# k1fm-pico-balloon-v1_2.net
KiCad netlist of a schematic drawn in EAGLE
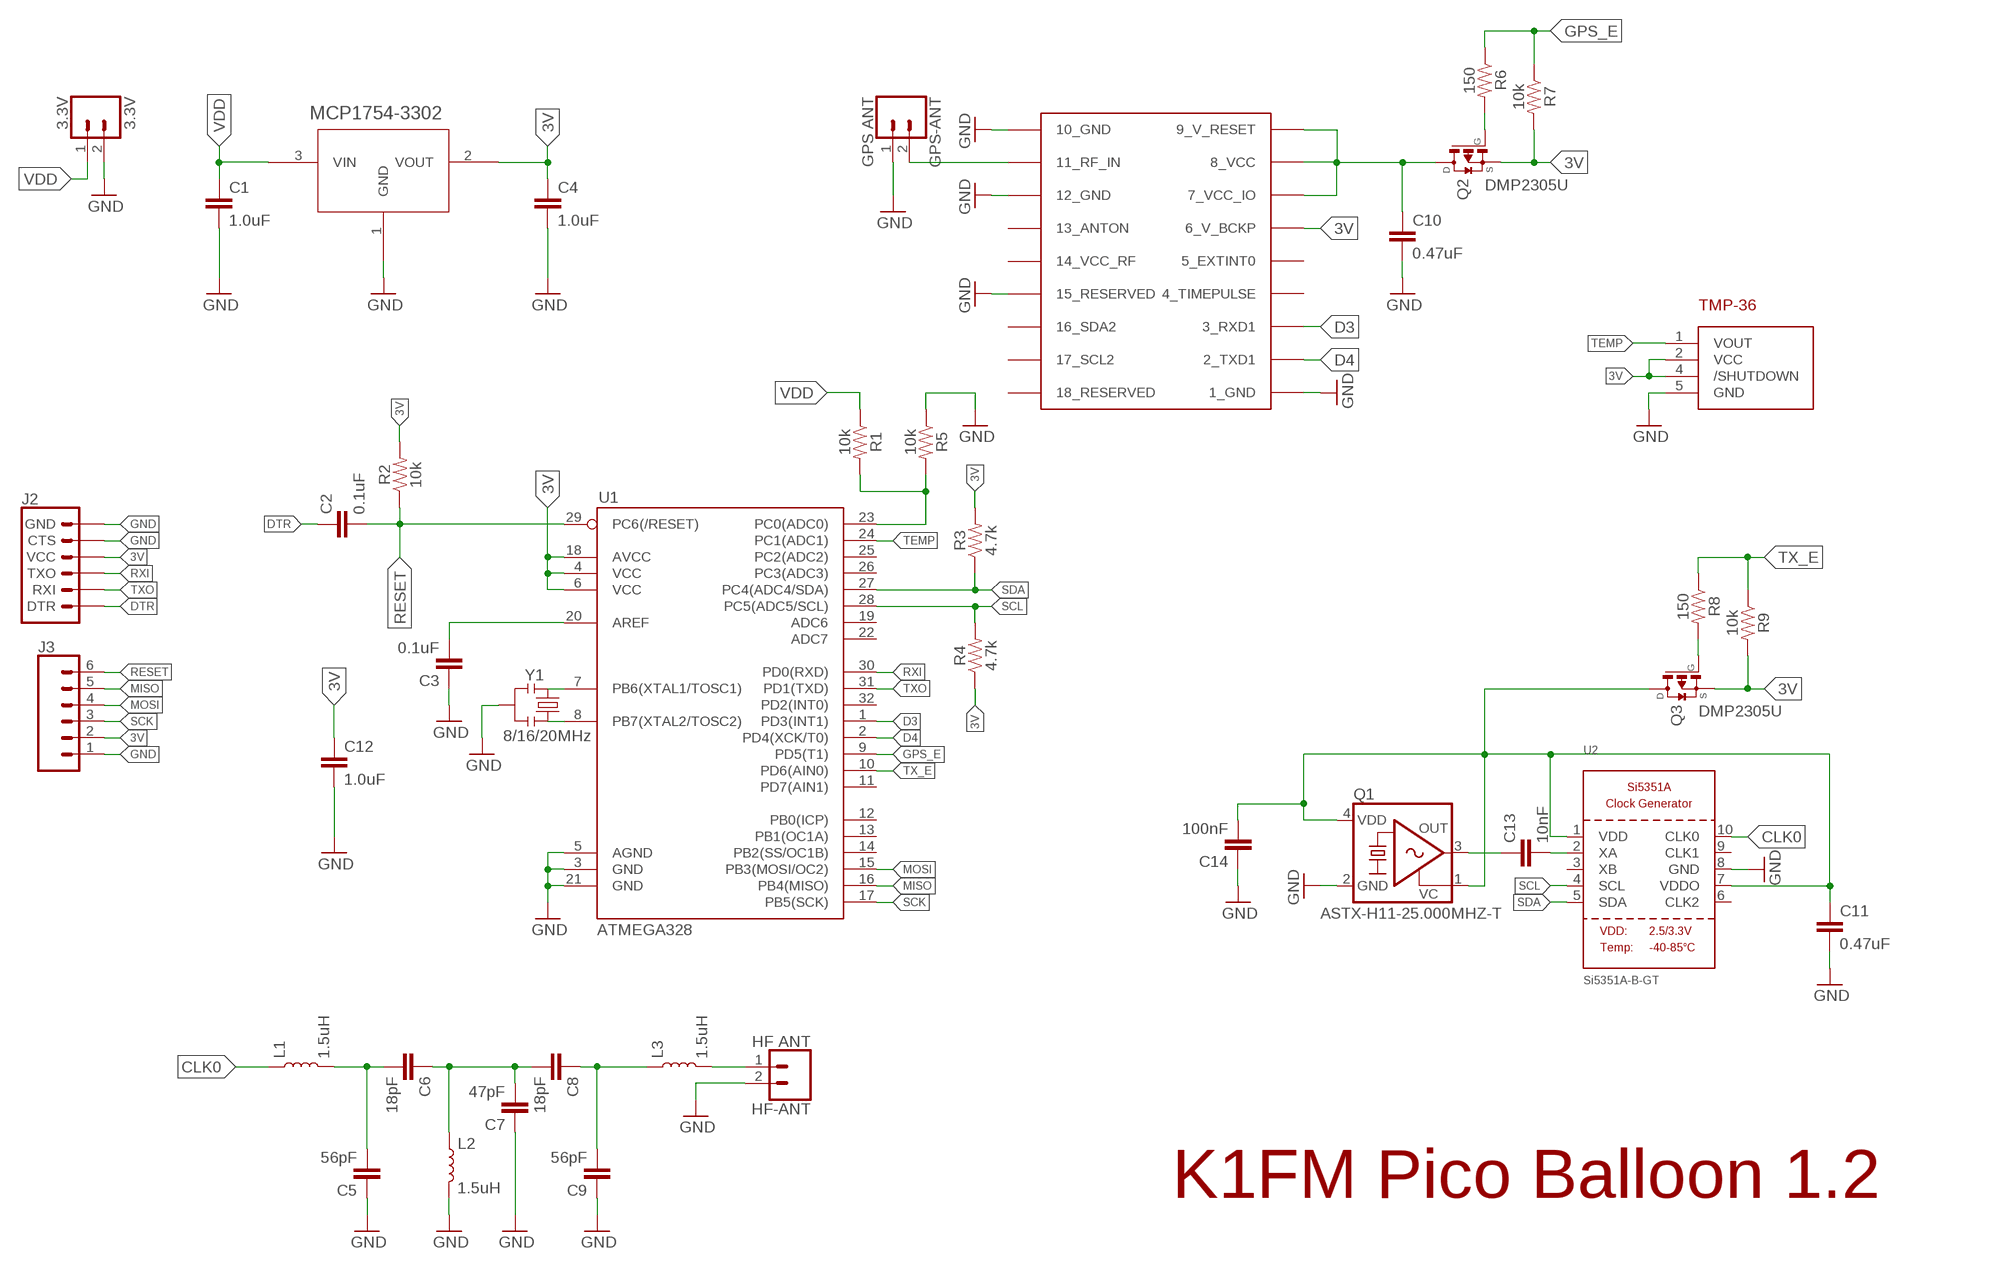
[diagram p0: schematic, sheet 1]

(export (version "E")
  (design (tool "Eeschema 10.0.6"))
  (components
    (comp (ref "3.3V")
      (value "3.3V")
      (footprint "eagle-import:1X02")
      (libsource (lib "eagle-import") (part "CONN_02"))
    )
    (comp (ref "C1")
      (value "1.0uF")
      (footprint "eagle-import:0603")
      (libsource (lib "eagle-import") (part "1.0UF-0603-16V-10%"))
    )
    (comp (ref "C2")
      (value "0.1uF")
      (footprint "eagle-import:0603")
      (libsource (lib "eagle-import") (part "0.1UF-0603-25V-5%"))
    )
    (comp (ref "C3")
      (value "0.1uF")
      (footprint "eagle-import:0603")
      (libsource (lib "eagle-import") (part "0.1UF-0603-25V-5%"))
    )
    (comp (ref "C4")
      (value "1.0uF")
      (footprint "eagle-import:0603")
      (libsource (lib "eagle-import") (part "1.0UF-0603-16V-10%"))
    )
    (comp (ref "C5")
      (value "56pF")
      (footprint "eagle-import:0603")
      (libsource (lib "eagle-import") (part "0.1UF-0603-25V-5%"))
    )
    (comp (ref "C6")
      (value "18pF")
      (footprint "eagle-import:0603")
      (libsource (lib "eagle-import") (part "0.1UF-0603-25V-5%"))
    )
    (comp (ref "C7")
      (value "47pF")
      (footprint "eagle-import:0603")
      (libsource (lib "eagle-import") (part "0.1UF-0603-25V-5%"))
    )
    (comp (ref "C8")
      (value "18pF")
      (footprint "eagle-import:0603")
      (libsource (lib "eagle-import") (part "0.1UF-0603-25V-5%"))
    )
    (comp (ref "C9")
      (value "56pF")
      (footprint "eagle-import:0603")
      (libsource (lib "eagle-import") (part "0.1UF-0603-25V-5%"))
    )
    (comp (ref "C10")
      (value "0.47uF")
      (footprint "eagle-import:0603")
      (libsource (lib "eagle-import") (part "0.1UF-0603-25V-5%"))
    )
    (comp (ref "C11")
      (value "0.47uF")
      (footprint "eagle-import:0603")
      (libsource (lib "eagle-import") (part "0.1UF-0603-25V-5%"))
    )
    (comp (ref "C12")
      (value "1.0uF")
      (footprint "eagle-import:0603")
      (libsource (lib "eagle-import") (part "1.0UF-0603-16V-10%"))
    )
    (comp (ref "C13")
      (value "10nF")
      (footprint "eagle-import:0603")
      (libsource (lib "eagle-import") (part "10NF-0603-50V-10%"))
    )
    (comp (ref "C14")
      (value "100nF")
      (footprint "eagle-import:0603")
      (libsource (lib "eagle-import") (part "10NF-0603-50V-10%"))
    )
    (comp (ref "GPS-ANT")
      (value "GPS ANT")
      (footprint "eagle-import:1X02")
      (libsource (lib "eagle-import") (part "CONN_02"))
    )
    (comp (ref "GPS1")
      (value "UBLOX_MAX")
      (footprint "eagle-import:UBLOX_MAX")
      (libsource (lib "eagle-import") (part "UBLOX_MAX"))
    )
    (comp (ref "HF-ANT")
      (value "HF ANT")
      (footprint "eagle-import:1X02")
      (libsource (lib "eagle-import") (part "CONN_02"))
    )
    (comp (ref "J2")
      (value "6_PIN_SERIAL_TARGET")
      (footprint "eagle-import:1X06")
      (libsource (lib "eagle-import") (part "6_PIN_SERIAL_TARGET"))
    )
    (comp (ref "J3")
      (value "CONN_06SILK_FEMALE_PTH")
      (footprint "eagle-import:1X06")
      (libsource (lib "eagle-import") (part "CONN_06SILK_FEMALE_PTH"))
    )
    (comp (ref "L1")
      (value "1.5uH")
      (footprint "eagle-import:0603")
      (libsource (lib "eagle-import") (part "INDUCTOR-0603-33NH"))
    )
    (comp (ref "L2")
      (value "1.5uH")
      (footprint "eagle-import:0603")
      (libsource (lib "eagle-import") (part "INDUCTOR-0603-33NH"))
    )
    (comp (ref "L3")
      (value "1.5uH")
      (footprint "eagle-import:0603")
      (libsource (lib "eagle-import") (part "INDUCTOR-0603-33NH"))
    )
    (comp (ref "Q1")
      (value "ASTX-H11-25.000MHZ-T")
      (footprint "eagle-import:3.2X2.5_KXO-84")
      (libsource (lib "eagle-import") (part "KXO-VCXO-SINE-84"))
    )
    (comp (ref "Q2")
      (value "DMP2305U")
      (footprint "eagle-import:SOT23")
      (libsource (lib "eagle-import") (part "DMP2305U"))
    )
    (comp (ref "Q3")
      (value "DMP2305U")
      (footprint "eagle-import:SOT23")
      (libsource (lib "eagle-import") (part "DMP2305U"))
    )
    (comp (ref "R1")
      (value "10k")
      (footprint "eagle-import:0603")
      (libsource (lib "eagle-import") (part "10KOHM-0603-1/10W-1%"))
    )
    (comp (ref "R2")
      (value "10k")
      (footprint "eagle-import:0603")
      (libsource (lib "eagle-import") (part "10KOHM-0603-1/10W-1%"))
    )
    (comp (ref "R3")
      (value "4.7k")
      (footprint "eagle-import:0603")
      (libsource (lib "eagle-import") (part "4.7KOHM-0603-1/10W-1%"))
    )
    (comp (ref "R4")
      (value "4.7k")
      (footprint "eagle-import:0603")
      (libsource (lib "eagle-import") (part "4.7KOHM-0603-1/10W-1%"))
    )
    (comp (ref "R5")
      (value "10k")
      (footprint "eagle-import:0603")
      (libsource (lib "eagle-import") (part "10KOHM-0603-1/10W-1%"))
    )
    (comp (ref "R6")
      (value "150")
      (footprint "eagle-import:0603")
      (libsource (lib "eagle-import") (part "10KOHM-0603-1/10W-1%"))
    )
    (comp (ref "R7")
      (value "10k")
      (footprint "eagle-import:0603")
      (libsource (lib "eagle-import") (part "10KOHM-0603-1/10W-1%"))
    )
    (comp (ref "R8")
      (value "150")
      (footprint "eagle-import:0603")
      (libsource (lib "eagle-import") (part "10KOHM-0603-1/10W-1%"))
    )
    (comp (ref "R9")
      (value "10k")
      (footprint "eagle-import:0603")
      (libsource (lib "eagle-import") (part "10KOHM-0603-1/10W-1%"))
    )
    (comp (ref "U1")
      (value "ATMEGA328")
      (footprint "eagle-import:TQFP32-08")
      (libsource (lib "eagle-import") (part "ATMEGA168"))
    )
    (comp (ref "U2")
      (value "Si5351A-B-GT")
      (footprint "eagle-import:MSOP10")
      (libsource (lib "eagle-import") (part "SI5351A"))
    )
    (comp (ref "U3")
      (value "MCP1754X-XXXXX/C")
      (footprint "eagle-import:SOT-23A_MC")
      (libsource (lib "eagle-import") (part "MCP1754X-XXXXX/C"))
    )
    (comp (ref "U4")
      (value "TMP36")
      (footprint "eagle-import:SOT-23")
      (libsource (lib "eagle-import") (part "TMP36"))
    )
    (comp (ref "Y1")
      (value "8/16/20MHz")
      (footprint "eagle-import:RESONATOR-SMD-1_1")
      (libsource (lib "eagle-import") (part "RESONATOR1{colon}1"))
    )
  )
  (nets
    (net (code "1") (name "3V") (class "Default")
      (node (ref "C12") (pin "1") (pinfunction "1_1") (pintype "passive"))
      (node (ref "C4") (pin "1") (pinfunction "1_1") (pintype "passive"))
      (node (ref "GPS1") (pin "6_V_BCKP") (pinfunction "6_V_BCKP_6_V_BCKP") (pintype "bidirectional"))
      (node (ref "J2") (pin "4") (pinfunction "VCC_4") (pintype "passive"))
      (node (ref "J3") (pin "2") (pinfunction "2_2") (pintype "passive"))
      (node (ref "Q2") (pin "2") (pinfunction "S_2") (pintype "passive"))
      (node (ref "Q3") (pin "2") (pinfunction "S_2") (pintype "passive"))
      (node (ref "R2") (pin "2") (pinfunction "2_2") (pintype "passive"))
      (node (ref "R3") (pin "2") (pinfunction "2_2") (pintype "passive"))
      (node (ref "R4") (pin "1") (pinfunction "1_1") (pintype "passive"))
      (node (ref "R7") (pin "2") (pinfunction "2_2") (pintype "passive"))
      (node (ref "R9") (pin "2") (pinfunction "2_2") (pintype "passive"))
      (node (ref "U1") (pin "18") (pinfunction "AVCC_18") (pintype "bidirectional"))
      (node (ref "U1") (pin "4") (pinfunction "VCC_4") (pintype "bidirectional"))
      (node (ref "U1") (pin "6") (pinfunction "VCC_6") (pintype "bidirectional"))
      (node (ref "U3") (pin "2") (pinfunction "VOUT_2") (pintype "passive"))
      (node (ref "U4") (pin "2") (pinfunction "VCC_2") (pintype "bidirectional"))
      (node (ref "U4") (pin "4") (pinfunction "/SHUTDOWN_4") (pintype "bidirectional"))
    )
    (net (code "2") (name "CLK0") (class "Default")
      (node (ref "L1") (pin "1") (pinfunction "1_1") (pintype "passive"))
      (node (ref "U2") (pin "10") (pinfunction "CLK0_10") (pintype "output"))
    )
    (net (code "3") (name "D3") (class "Default")
      (node (ref "GPS1") (pin "3_RXD1") (pinfunction "3_RXD1_3_RXD1") (pintype "bidirectional"))
      (node (ref "U1") (pin "1") (pinfunction "PD3(INT1)_1") (pintype "bidirectional"))
    )
    (net (code "4") (name "D4") (class "Default")
      (node (ref "GPS1") (pin "2_TXD1") (pinfunction "2_TXD1_2_TXD1") (pintype "bidirectional"))
      (node (ref "U1") (pin "2") (pinfunction "PD4(XCK/T0)_2") (pintype "bidirectional"))
    )
    (net (code "5") (name "DTR") (class "Default")
      (node (ref "C2") (pin "1") (pinfunction "1_1") (pintype "passive"))
      (node (ref "J2") (pin "1") (pinfunction "DTR_1") (pintype "passive"))
    )
    (net (code "6") (name "GND") (class "Default")
      (node (ref "3.3V") (pin "2") (pinfunction "2_2") (pintype "passive"))
      (node (ref "C1") (pin "2") (pinfunction "2_2") (pintype "passive"))
      (node (ref "C10") (pin "2") (pinfunction "2_2") (pintype "passive"))
      (node (ref "C11") (pin "2") (pinfunction "2_2") (pintype "passive"))
      (node (ref "C12") (pin "2") (pinfunction "2_2") (pintype "passive"))
      (node (ref "C14") (pin "1") (pinfunction "1_1") (pintype "passive"))
      (node (ref "C3") (pin "1") (pinfunction "1_1") (pintype "passive"))
      (node (ref "C4") (pin "2") (pinfunction "2_2") (pintype "passive"))
      (node (ref "C5") (pin "1") (pinfunction "1_1") (pintype "passive"))
      (node (ref "C7") (pin "1") (pinfunction "1_1") (pintype "passive"))
      (node (ref "C9") (pin "1") (pinfunction "1_1") (pintype "passive"))
      (node (ref "GPS-ANT") (pin "1") (pinfunction "1_1") (pintype "passive"))
      (node (ref "GPS1") (pin "10_GND") (pinfunction "10_GND_10_GND") (pintype "power_in"))
      (node (ref "GPS1") (pin "12_GND") (pinfunction "12_GND_12_GND") (pintype "power_in"))
      (node (ref "GPS1") (pin "15_RESERVED") (pinfunction "15_RESERVED_15_RESERVED") (pintype "bidirectional"))
      (node (ref "GPS1") (pin "1_GND") (pinfunction "1_GND_1_GND") (pintype "power_in"))
      (node (ref "HF-ANT") (pin "2") (pinfunction "2_2") (pintype "passive"))
      (node (ref "J2") (pin "5") (pinfunction "CTS_5") (pintype "passive"))
      (node (ref "J2") (pin "6") (pinfunction "GND_6") (pintype "passive"))
      (node (ref "J3") (pin "1") (pinfunction "1_1") (pintype "passive"))
      (node (ref "L2") (pin "2") (pinfunction "2_2") (pintype "passive"))
      (node (ref "Q1") (pin "2") (pinfunction "GND_2") (pintype "power_in"))
      (node (ref "R5") (pin "1") (pinfunction "1_1") (pintype "passive"))
      (node (ref "U1") (pin "21") (pinfunction "GND_21") (pintype "bidirectional"))
      (node (ref "U1") (pin "3") (pinfunction "GND_3") (pintype "bidirectional"))
      (node (ref "U1") (pin "5") (pinfunction "AGND_5") (pintype "bidirectional"))
      (node (ref "U2") (pin "8") (pinfunction "GND_8") (pintype "power_in"))
      (node (ref "U3") (pin "1") (pinfunction "GND_1") (pintype "passive"))
      (node (ref "U4") (pin "5") (pinfunction "GND_5") (pintype "bidirectional"))
      (node (ref "Y1") (pin "2") (pinfunction "2_2") (pintype "passive"))
    )
    (net (code "7") (name "GPS_E") (class "Default")
      (node (ref "R6") (pin "1") (pinfunction "1_1") (pintype "passive"))
      (node (ref "R7") (pin "1") (pinfunction "1_1") (pintype "passive"))
      (node (ref "U1") (pin "9") (pinfunction "PD5(T1)_9") (pintype "bidirectional"))
    )
    (net (code "8") (name "MISO") (class "Default")
      (node (ref "J3") (pin "5") (pinfunction "5_5") (pintype "passive"))
      (node (ref "U1") (pin "16") (pinfunction "PB4(MISO)_16") (pintype "bidirectional"))
    )
    (net (code "9") (name "MOSI") (class "Default")
      (node (ref "J3") (pin "4") (pinfunction "4_4") (pintype "passive"))
      (node (ref "U1") (pin "15") (pinfunction "PB3(MOSI/OC2)_15") (pintype "bidirectional"))
    )
    (net (code "10") (name "Net-(C5-Pad2)") (class "Default")
      (node (ref "C5") (pin "2") (pinfunction "2_2") (pintype "passive"))
      (node (ref "C6") (pin "2") (pinfunction "2_2") (pintype "passive"))
      (node (ref "L1") (pin "2") (pinfunction "2_2") (pintype "passive"))
    )
    (net (code "11") (name "Net-(C6-Pad1)") (class "Default")
      (node (ref "C6") (pin "1") (pinfunction "1_1") (pintype "passive"))
      (node (ref "C7") (pin "2") (pinfunction "2_2") (pintype "passive"))
      (node (ref "C8") (pin "2") (pinfunction "2_2") (pintype "passive"))
      (node (ref "L2") (pin "1") (pinfunction "1_1") (pintype "passive"))
    )
    (net (code "12") (name "Net-(C8-Pad1)") (class "Default")
      (node (ref "C8") (pin "1") (pinfunction "1_1") (pintype "passive"))
      (node (ref "C9") (pin "2") (pinfunction "2_2") (pintype "passive"))
      (node (ref "L3") (pin "1") (pinfunction "1_1") (pintype "passive"))
    )
    (net (code "13") (name "Net-(GPS-ANT-Pad2)") (class "Default")
      (node (ref "GPS-ANT") (pin "2") (pinfunction "2_2") (pintype "passive"))
      (node (ref "GPS1") (pin "11_RF_IN") (pinfunction "11_RF_IN_11_RF_IN") (pintype "bidirectional"))
    )
    (net (code "14") (name "Net-(HF-ANT-Pad1)") (class "Default")
      (node (ref "HF-ANT") (pin "1") (pinfunction "1_1") (pintype "passive"))
      (node (ref "L3") (pin "2") (pinfunction "2_2") (pintype "passive"))
    )
    (net (code "15") (name "Net-(Q1-OUT)") (class "Default")
      (node (ref "C13") (pin "1") (pinfunction "1_1") (pintype "passive"))
      (node (ref "Q1") (pin "3") (pinfunction "OUT_3") (pintype "output"))
    )
    (net (code "16") (name "Net-(Q1-VC)") (class "Default")
      (node (ref "C11") (pin "1") (pinfunction "1_1") (pintype "passive"))
      (node (ref "C14") (pin "2") (pinfunction "2_2") (pintype "passive"))
      (node (ref "Q1") (pin "1") (pinfunction "VC_1") (pintype "input"))
      (node (ref "Q1") (pin "4") (pinfunction "VDD_4") (pintype "power_in"))
      (node (ref "Q3") (pin "3") (pinfunction "D_3") (pintype "passive"))
      (node (ref "U2") (pin "1") (pinfunction "VDD_1") (pintype "power_in"))
      (node (ref "U2") (pin "7") (pinfunction "VDDO_7") (pintype "power_in"))
    )
    (net (code "17") (name "Net-(Q2-D)") (class "Default")
      (node (ref "C10") (pin "1") (pinfunction "1_1") (pintype "passive"))
      (node (ref "GPS1") (pin "7_VCC_IO") (pinfunction "7_VCC_IO_7_VCC_IO") (pintype "power_in"))
      (node (ref "GPS1") (pin "8_VCC") (pinfunction "8_VCC_8_VCC") (pintype "power_in"))
      (node (ref "GPS1") (pin "9_V_RESET") (pinfunction "9_V_RESET_9_V_RESET") (pintype "power_in"))
      (node (ref "Q2") (pin "3") (pinfunction "D_3") (pintype "passive"))
    )
    (net (code "18") (name "Net-(Q2-G)") (class "Default")
      (node (ref "Q2") (pin "1") (pinfunction "G_1") (pintype "passive"))
      (node (ref "R6") (pin "2") (pinfunction "2_2") (pintype "passive"))
    )
    (net (code "19") (name "Net-(Q3-G)") (class "Default")
      (node (ref "Q3") (pin "1") (pinfunction "G_1") (pintype "passive"))
      (node (ref "R8") (pin "2") (pinfunction "2_2") (pintype "passive"))
    )
    (net (code "20") (name "Net-(U1-AREF)") (class "Default")
      (node (ref "C3") (pin "2") (pinfunction "2_2") (pintype "passive"))
      (node (ref "U1") (pin "20") (pinfunction "AREF_20") (pintype "bidirectional"))
    )
    (net (code "21") (name "Net-(U1-PB6(XTAL1{slash}TOSC1))") (class "Default")
      (node (ref "U1") (pin "7") (pinfunction "PB6(XTAL1/TOSC1)_7") (pintype "bidirectional"))
      (node (ref "Y1") (pin "1") (pinfunction "1_1") (pintype "passive"))
    )
    (net (code "22") (name "Net-(U1-PB7(XTAL2{slash}TOSC2))") (class "Default")
      (node (ref "U1") (pin "8") (pinfunction "PB7(XTAL2/TOSC2)_8") (pintype "bidirectional"))
      (node (ref "Y1") (pin "3") (pinfunction "3_3") (pintype "passive"))
    )
    (net (code "23") (name "Net-(U1-PC0(ADC0))") (class "Default")
      (node (ref "R1") (pin "2") (pinfunction "2_2") (pintype "passive"))
      (node (ref "R5") (pin "2") (pinfunction "2_2") (pintype "passive"))
      (node (ref "U1") (pin "23") (pinfunction "PC0(ADC0)_23") (pintype "bidirectional"))
    )
    (net (code "24") (name "Net-(U2-XA)") (class "Default")
      (node (ref "C13") (pin "2") (pinfunction "2_2") (pintype "passive"))
      (node (ref "U2") (pin "2") (pinfunction "XA_2") (pintype "input"))
    )
    (net (code "25") (name "RESET") (class "Default")
      (node (ref "C2") (pin "2") (pinfunction "2_2") (pintype "passive"))
      (node (ref "J3") (pin "6") (pinfunction "6_6") (pintype "passive"))
      (node (ref "R2") (pin "1") (pinfunction "1_1") (pintype "passive"))
      (node (ref "U1") (pin "29") (pinfunction "PC6(/RESET)_29") (pintype "bidirectional"))
    )
    (net (code "26") (name "RXI") (class "Default")
      (node (ref "J2") (pin "3") (pinfunction "TXO_3") (pintype "passive"))
      (node (ref "U1") (pin "30") (pinfunction "PD0(RXD)_30") (pintype "bidirectional"))
    )
    (net (code "27") (name "SCK") (class "Default")
      (node (ref "J3") (pin "3") (pinfunction "3_3") (pintype "passive"))
      (node (ref "U1") (pin "17") (pinfunction "PB5(SCK)_17") (pintype "bidirectional"))
    )
    (net (code "28") (name "SCL") (class "Default")
      (node (ref "R4") (pin "2") (pinfunction "2_2") (pintype "passive"))
      (node (ref "U1") (pin "28") (pinfunction "PC5(ADC5/SCL)_28") (pintype "bidirectional"))
      (node (ref "U2") (pin "4") (pinfunction "SCL_4") (pintype "input"))
    )
    (net (code "29") (name "SDA") (class "Default")
      (node (ref "R3") (pin "1") (pinfunction "1_1") (pintype "passive"))
      (node (ref "U1") (pin "27") (pinfunction "PC4(ADC4/SDA)_27") (pintype "bidirectional"))
      (node (ref "U2") (pin "5") (pinfunction "SDA_5") (pintype "bidirectional"))
    )
    (net (code "30") (name "TEMP") (class "Default")
      (node (ref "U1") (pin "24") (pinfunction "PC1(ADC1)_24") (pintype "bidirectional"))
      (node (ref "U4") (pin "1") (pinfunction "VOUT_1") (pintype "bidirectional"))
    )
    (net (code "31") (name "TXO") (class "Default")
      (node (ref "J2") (pin "2") (pinfunction "RXI_2") (pintype "passive"))
      (node (ref "U1") (pin "31") (pinfunction "PD1(TXD)_31") (pintype "bidirectional"))
    )
    (net (code "32") (name "TX_E") (class "Default")
      (node (ref "R8") (pin "1") (pinfunction "1_1") (pintype "passive"))
      (node (ref "R9") (pin "1") (pinfunction "1_1") (pintype "passive"))
      (node (ref "U1") (pin "10") (pinfunction "PD6(AIN0)_10") (pintype "bidirectional"))
    )
    (net (code "33") (name "VDD") (class "Default")
      (node (ref "3.3V") (pin "1") (pinfunction "1_1") (pintype "passive"))
      (node (ref "C1") (pin "1") (pinfunction "1_1") (pintype "passive"))
      (node (ref "R1") (pin "1") (pinfunction "1_1") (pintype "passive"))
      (node (ref "U3") (pin "3") (pinfunction "VIN_3") (pintype "passive"))
    )
    (net (code "34") (name "unconnected-(GPS1-Pad4_TIMEPULSE)") (class "Default")
      (node (ref "GPS1") (pin "4_TIMEPULSE") (pinfunction "4_TIMEPULSE_4_TIMEPULSE") (pintype "bidirectional"))
    )
    (net (code "35") (name "unconnected-(GPS1-Pad5_EXTINT0)") (class "Default")
      (node (ref "GPS1") (pin "5_EXTINT0") (pinfunction "5_EXTINT0_5_EXTINT0") (pintype "bidirectional"))
    )
    (net (code "36") (name "unconnected-(GPS1-Pad13_ANTON)") (class "Default")
      (node (ref "GPS1") (pin "13_ANTON") (pinfunction "13_ANTON_13_ANTON") (pintype "bidirectional"))
    )
    (net (code "37") (name "unconnected-(GPS1-Pad14_VCC_RF)") (class "Default")
      (node (ref "GPS1") (pin "14_VCC_RF") (pinfunction "14_VCC_RF_14_VCC_RF") (pintype "bidirectional"))
    )
    (net (code "38") (name "unconnected-(GPS1-Pad16_SDA2)") (class "Default")
      (node (ref "GPS1") (pin "16_SDA2") (pinfunction "16_SDA2_16_SDA2") (pintype "bidirectional"))
    )
    (net (code "39") (name "unconnected-(GPS1-Pad17_SCL2)") (class "Default")
      (node (ref "GPS1") (pin "17_SCL2") (pinfunction "17_SCL2_17_SCL2") (pintype "bidirectional"))
    )
    (net (code "40") (name "unconnected-(GPS1-Pad18_RESERVED)") (class "Default")
      (node (ref "GPS1") (pin "18_RESERVED") (pinfunction "18_RESERVED_18_RESERVED") (pintype "bidirectional"))
    )
    (net (code "41") (name "unconnected-(U1-ADC6-Pad19)") (class "Default")
      (node (ref "U1") (pin "19") (pinfunction "ADC6_19") (pintype "bidirectional"))
    )
    (net (code "42") (name "unconnected-(U1-ADC7-Pad22)") (class "Default")
      (node (ref "U1") (pin "22") (pinfunction "ADC7_22") (pintype "bidirectional"))
    )
    (net (code "43") (name "unconnected-(U1-PB0(ICP)-Pad12)") (class "Default")
      (node (ref "U1") (pin "12") (pinfunction "PB0(ICP)_12") (pintype "bidirectional"))
    )
    (net (code "44") (name "unconnected-(U1-PB1(OC1A)-Pad13)") (class "Default")
      (node (ref "U1") (pin "13") (pinfunction "PB1(OC1A)_13") (pintype "bidirectional"))
    )
    (net (code "45") (name "unconnected-(U1-PB2(SS{slash}OC1B)-Pad14)") (class "Default")
      (node (ref "U1") (pin "14") (pinfunction "PB2(SS/OC1B)_14") (pintype "bidirectional"))
    )
    (net (code "46") (name "unconnected-(U1-PC2(ADC2)-Pad25)") (class "Default")
      (node (ref "U1") (pin "25") (pinfunction "PC2(ADC2)_25") (pintype "bidirectional"))
    )
    (net (code "47") (name "unconnected-(U1-PC3(ADC3)-Pad26)") (class "Default")
      (node (ref "U1") (pin "26") (pinfunction "PC3(ADC3)_26") (pintype "bidirectional"))
    )
    (net (code "48") (name "unconnected-(U1-PD2(INT0)-Pad32)") (class "Default")
      (node (ref "U1") (pin "32") (pinfunction "PD2(INT0)_32") (pintype "bidirectional"))
    )
    (net (code "49") (name "unconnected-(U1-PD7(AIN1)-Pad11)") (class "Default")
      (node (ref "U1") (pin "11") (pinfunction "PD7(AIN1)_11") (pintype "bidirectional"))
    )
    (net (code "50") (name "unconnected-(U2-CLK1-Pad9)") (class "Default")
      (node (ref "U2") (pin "9") (pinfunction "CLK1_9") (pintype "output"))
    )
    (net (code "51") (name "unconnected-(U2-CLK2-Pad6)") (class "Default")
      (node (ref "U2") (pin "6") (pinfunction "CLK2_6") (pintype "output"))
    )
    (net (code "52") (name "unconnected-(U2-XB-Pad3)") (class "Default")
      (node (ref "U2") (pin "3") (pinfunction "XB_3") (pintype "input"))
    )
  )
)
